# SCH.net
KiCad netlist of a schematic drawn in EasyEDA
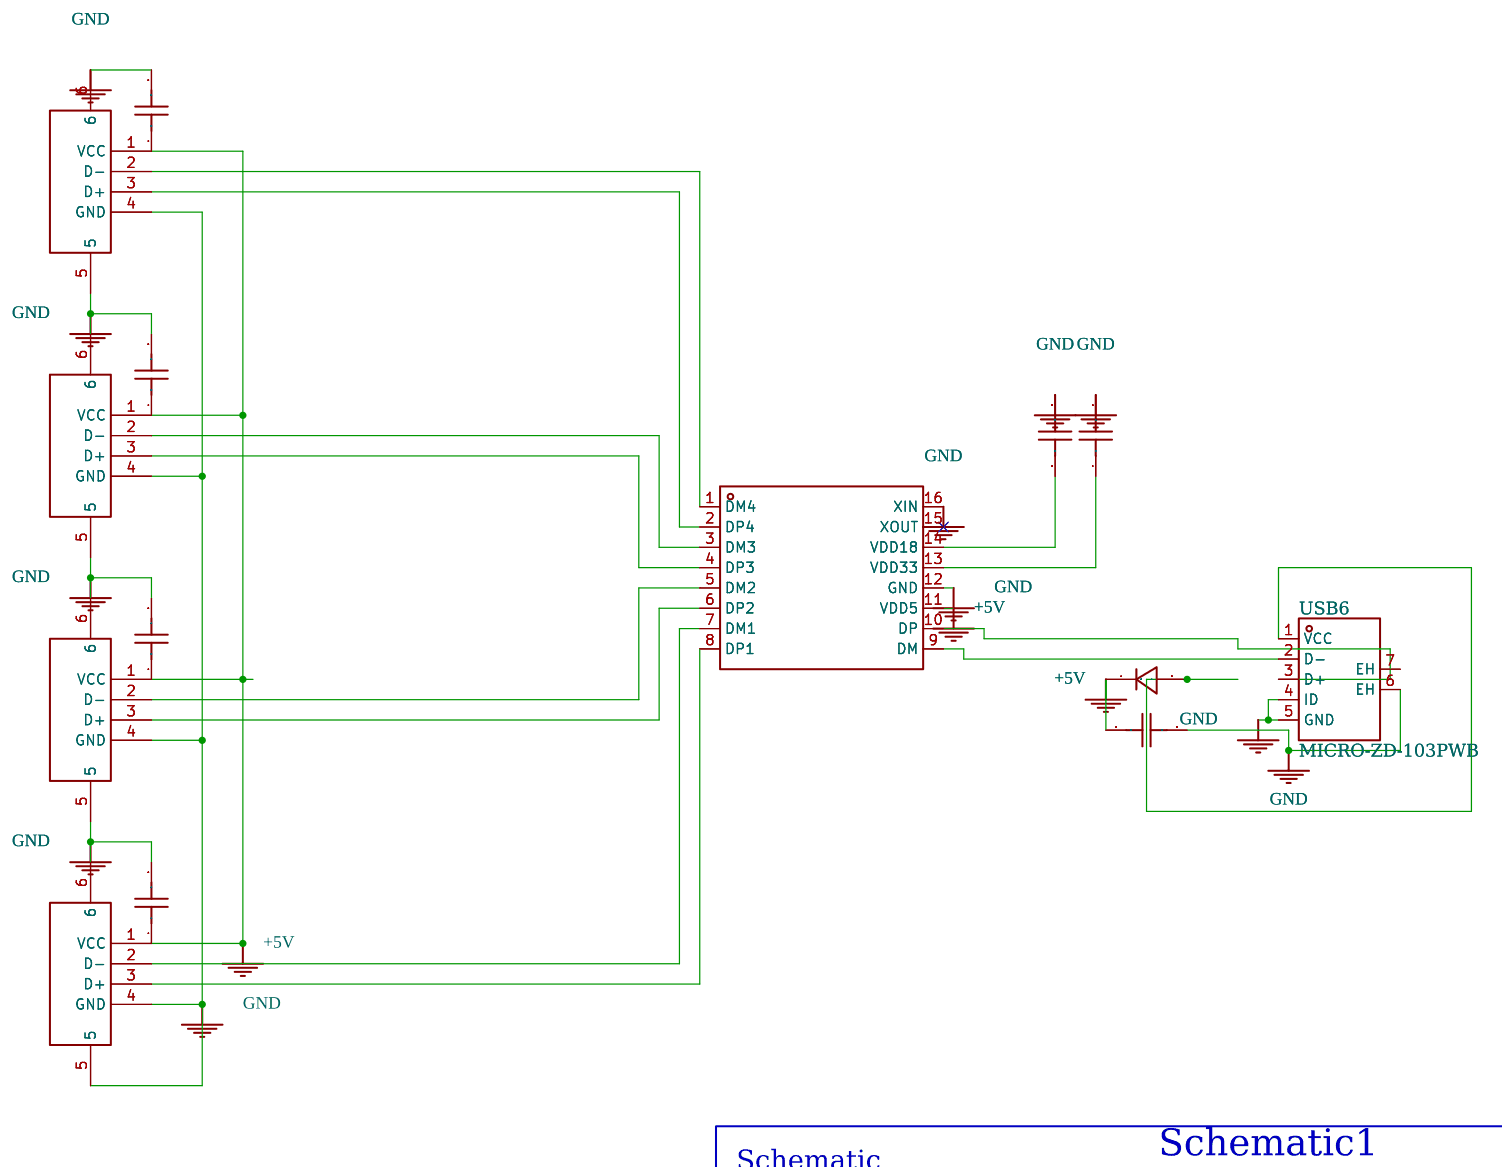
[diagram p0: schematic sheet]

(export (version "E")
  (design (tool "Eeschema 10.0.6"))
  (components
    (comp (ref "C1")
      (value "10uF")
      (fields
        (field (name "Manufacturer Part") "CL10A106KP8NNNC")
        (field (name "Manufacturer") "SAMSUNG(三星)")
      )
      (libsource (lib "") (part "Unknown_700_-415"))
    )
    (comp (ref "C2")
      (value "10uF")
      (fields
        (field (name "Manufacturer Part") "CL10A106KP8NNNC")
        (field (name "Manufacturer") "SAMSUNG(三星)")
      )
      (libsource (lib "") (part "Unknown_675_-560"))
    )
    (comp (ref "C3")
      (value "10uF")
      (fields
        (field (name "Manufacturer Part") "CL10A106KP8NNNC")
        (field (name "Manufacturer") "SAMSUNG(三星)")
      )
      (libsource (lib "") (part "Unknown_655_-560"))
    )
    (comp (ref "C4")
      (value "10uF")
      (fields
        (field (name "Manufacturer Part") "CL10A106KP8NNNC")
        (field (name "Manufacturer") "SAMSUNG(三星)")
      )
      (libsource (lib "") (part "Unknown_210_-460"))
    )
    (comp (ref "C5")
      (value "10uF")
      (fields
        (field (name "Manufacturer Part") "CL10A106KP8NNNC")
        (field (name "Manufacturer") "SAMSUNG(三星)")
      )
      (libsource (lib "") (part "Unknown_210_-330"))
    )
    (comp (ref "C6")
      (value "10uF")
      (fields
        (field (name "Manufacturer Part") "CL10A106KP8NNNC")
        (field (name "Manufacturer") "SAMSUNG(三星)")
      )
      (libsource (lib "") (part "Unknown_210_-720"))
    )
    (comp (ref "C7")
      (value "10uF")
      (fields
        (field (name "Manufacturer Part") "CL10A106KP8NNNC")
        (field (name "Manufacturer") "SAMSUNG(三星)")
      )
      (libsource (lib "") (part "Unknown_210_-590"))
    )
    (comp (ref "D1")
      (value "NSR0320MW2T1G")
      (fields (field (name "Manufacturer") "onsemi(安森美)"))
      (libsource (lib "") (part "Unknown_700_-440"))
    )
    (comp (ref "U1")
      (value "SL2.1A")
      (fields (field (name "Manufacturer") "CoreChips(和芯润德)"))
      (libsource (lib "") (part "Unknown_540_-490"))
    )
    (comp (ref "USB2")
      (value "903-131A1011D10100")
      (fields (field (name "Manufacturer") "精拓金"))
      (libsource (lib "") (part "Unknown_190_-680"))
    )
    (comp (ref "USB3")
      (value "903-131A1011D10100")
      (fields (field (name "Manufacturer") "精拓金"))
      (libsource (lib "") (part "Unknown_190_-550"))
    )
    (comp (ref "USB4")
      (value "903-131A1011D10100")
      (fields (field (name "Manufacturer") "精拓金"))
      (libsource (lib "") (part "Unknown_190_-420"))
    )
    (comp (ref "USB5")
      (value "903-131A1011D10100")
      (fields (field (name "Manufacturer") "精拓金"))
      (libsource (lib "") (part "Unknown_190_-290"))
    )
    (comp (ref "USB6")
      (value "MICRO-ZD-103PWB")
      (fields (field (name "Manufacturer") "HDGC(华德共创)"))
      (libsource (lib "") (part "Unknown_790_-440"))
    )
  )
  (nets
    (net (code "1") (name "+5V") (class "Default")
      (node (ref "C1") (pin "1") (pinfunction "1_1") (pintype "unspecified"))
      (node (ref "C4") (pin "1") (pinfunction "1_1") (pintype "unspecified"))
      (node (ref "C5") (pin "1") (pinfunction "1_1") (pintype "unspecified"))
      (node (ref "C6") (pin "1") (pinfunction "1_1") (pintype "unspecified"))
      (node (ref "C7") (pin "1") (pinfunction "1_1") (pintype "unspecified"))
      (node (ref "D1") (pin "1") (pinfunction "C_1") (pintype "unspecified"))
      (node (ref "U1") (pin "11") (pinfunction "VDD5_11") (pintype "unspecified"))
      (node (ref "USB2") (pin "1") (pinfunction "VCC_1") (pintype "unspecified"))
      (node (ref "USB3") (pin "1") (pinfunction "VCC_1") (pintype "unspecified"))
      (node (ref "USB4") (pin "1") (pinfunction "VCC_1") (pintype "unspecified"))
      (node (ref "USB5") (pin "1") (pinfunction "VCC_1") (pintype "unspecified"))
    )
    (net (code "2") (name "GND") (class "Default")
      (node (ref "C1") (pin "2") (pinfunction "2_2") (pintype "unspecified"))
      (node (ref "C2") (pin "2") (pinfunction "2_2") (pintype "unspecified"))
      (node (ref "C3") (pin "2") (pinfunction "2_2") (pintype "unspecified"))
      (node (ref "C4") (pin "2") (pinfunction "2_2") (pintype "unspecified"))
      (node (ref "C5") (pin "2") (pinfunction "2_2") (pintype "unspecified"))
      (node (ref "C6") (pin "2") (pinfunction "2_2") (pintype "unspecified"))
      (node (ref "C7") (pin "2") (pinfunction "2_2") (pintype "unspecified"))
      (node (ref "U1") (pin "12") (pinfunction "GND_12") (pintype "unspecified"))
      (node (ref "U1") (pin "16") (pinfunction "XIN_16") (pintype "unspecified"))
      (node (ref "USB2") (pin "4") (pinfunction "GND_4") (pintype "unspecified"))
      (node (ref "USB2") (pin "5") (pinfunction "5_5") (pintype "unspecified"))
      (node (ref "USB2") (pin "6") (pinfunction "6_6") (pintype "unspecified"))
      (node (ref "USB3") (pin "4") (pinfunction "GND_4") (pintype "unspecified"))
      (node (ref "USB3") (pin "5") (pinfunction "5_5") (pintype "unspecified"))
      (node (ref "USB3") (pin "6") (pinfunction "6_6") (pintype "unspecified"))
      (node (ref "USB4") (pin "4") (pinfunction "GND_4") (pintype "unspecified"))
      (node (ref "USB4") (pin "5") (pinfunction "5_5") (pintype "unspecified"))
      (node (ref "USB4") (pin "6") (pinfunction "6_6") (pintype "unspecified"))
      (node (ref "USB5") (pin "4") (pinfunction "GND_4") (pintype "unspecified"))
      (node (ref "USB5") (pin "5") (pinfunction "5_5") (pintype "unspecified"))
      (node (ref "USB5") (pin "6") (pinfunction "6_6") (pintype "unspecified"))
      (node (ref "USB6") (pin "4") (pinfunction "ID_4") (pintype "unspecified"))
      (node (ref "USB6") (pin "5") (pinfunction "GND_5") (pintype "unspecified"))
      (node (ref "USB6") (pin "6") (pinfunction "EH_6") (pintype "unspecified"))
    )
    (net (code "3") (name "Net-(D1-A)") (class "Default")
      (node (ref "D1") (pin "2") (pinfunction "A_2") (pintype "unspecified"))
      (node (ref "USB6") (pin "1") (pinfunction "VCC_1") (pintype "unspecified"))
    )
    (net (code "4") (name "Net-(U1-DM)") (class "Default")
      (node (ref "U1") (pin "9") (pinfunction "DM_9") (pintype "unspecified"))
      (node (ref "USB6") (pin "2") (pinfunction "D-_2") (pintype "unspecified"))
    )
    (net (code "5") (name "Net-(U1-DM1)") (class "Default")
      (node (ref "U1") (pin "7") (pinfunction "DM1_7") (pintype "unspecified"))
      (node (ref "USB5") (pin "2") (pinfunction "D-_2") (pintype "unspecified"))
    )
    (net (code "6") (name "Net-(U1-DM2)") (class "Default")
      (node (ref "U1") (pin "5") (pinfunction "DM2_5") (pintype "unspecified"))
      (node (ref "USB4") (pin "2") (pinfunction "D-_2") (pintype "unspecified"))
    )
    (net (code "7") (name "Net-(U1-DM3)") (class "Default")
      (node (ref "U1") (pin "3") (pinfunction "DM3_3") (pintype "unspecified"))
      (node (ref "USB3") (pin "2") (pinfunction "D-_2") (pintype "unspecified"))
    )
    (net (code "8") (name "Net-(U1-DM4)") (class "Default")
      (node (ref "U1") (pin "1") (pinfunction "DM4_1") (pintype "unspecified"))
      (node (ref "USB2") (pin "2") (pinfunction "D-_2") (pintype "unspecified"))
    )
    (net (code "9") (name "Net-(U1-DP)") (class "Default")
      (node (ref "U1") (pin "10") (pinfunction "DP_10") (pintype "unspecified"))
      (node (ref "USB6") (pin "3") (pinfunction "D+_3") (pintype "unspecified"))
    )
    (net (code "10") (name "Net-(U1-DP1)") (class "Default")
      (node (ref "U1") (pin "8") (pinfunction "DP1_8") (pintype "unspecified"))
      (node (ref "USB5") (pin "3") (pinfunction "D+_3") (pintype "unspecified"))
    )
    (net (code "11") (name "Net-(U1-DP2)") (class "Default")
      (node (ref "U1") (pin "6") (pinfunction "DP2_6") (pintype "unspecified"))
      (node (ref "USB4") (pin "3") (pinfunction "D+_3") (pintype "unspecified"))
    )
    (net (code "12") (name "Net-(U1-DP3)") (class "Default")
      (node (ref "U1") (pin "4") (pinfunction "DP3_4") (pintype "unspecified"))
      (node (ref "USB3") (pin "3") (pinfunction "D+_3") (pintype "unspecified"))
    )
    (net (code "13") (name "Net-(U1-DP4)") (class "Default")
      (node (ref "U1") (pin "2") (pinfunction "DP4_2") (pintype "unspecified"))
      (node (ref "USB2") (pin "3") (pinfunction "D+_3") (pintype "unspecified"))
    )
    (net (code "14") (name "Net-(U1-VDD18)") (class "Default")
      (node (ref "C3") (pin "1") (pinfunction "1_1") (pintype "unspecified"))
      (node (ref "U1") (pin "14") (pinfunction "VDD18_14") (pintype "unspecified"))
    )
    (net (code "15") (name "Net-(U1-VDD33)") (class "Default")
      (node (ref "C2") (pin "1") (pinfunction "1_1") (pintype "unspecified"))
      (node (ref "U1") (pin "13") (pinfunction "VDD33_13") (pintype "unspecified"))
    )
    (net (code "16") (name "unconnected-(U1-XOUT-Pad15)") (class "Default")
      (node (ref "U1") (pin "15") (pinfunction "XOUT_15") (pintype "unspecified+no_connect"))
    )
    (net (code "17") (name "unconnected-(USB6-EH-Pad7)") (class "Default")
      (node (ref "USB6") (pin "7") (pinfunction "EH_7") (pintype "unspecified"))
    )
  )
)
